# Joystick-Minikarte.net
KiCad netlist of a schematic drawn in EAGLE
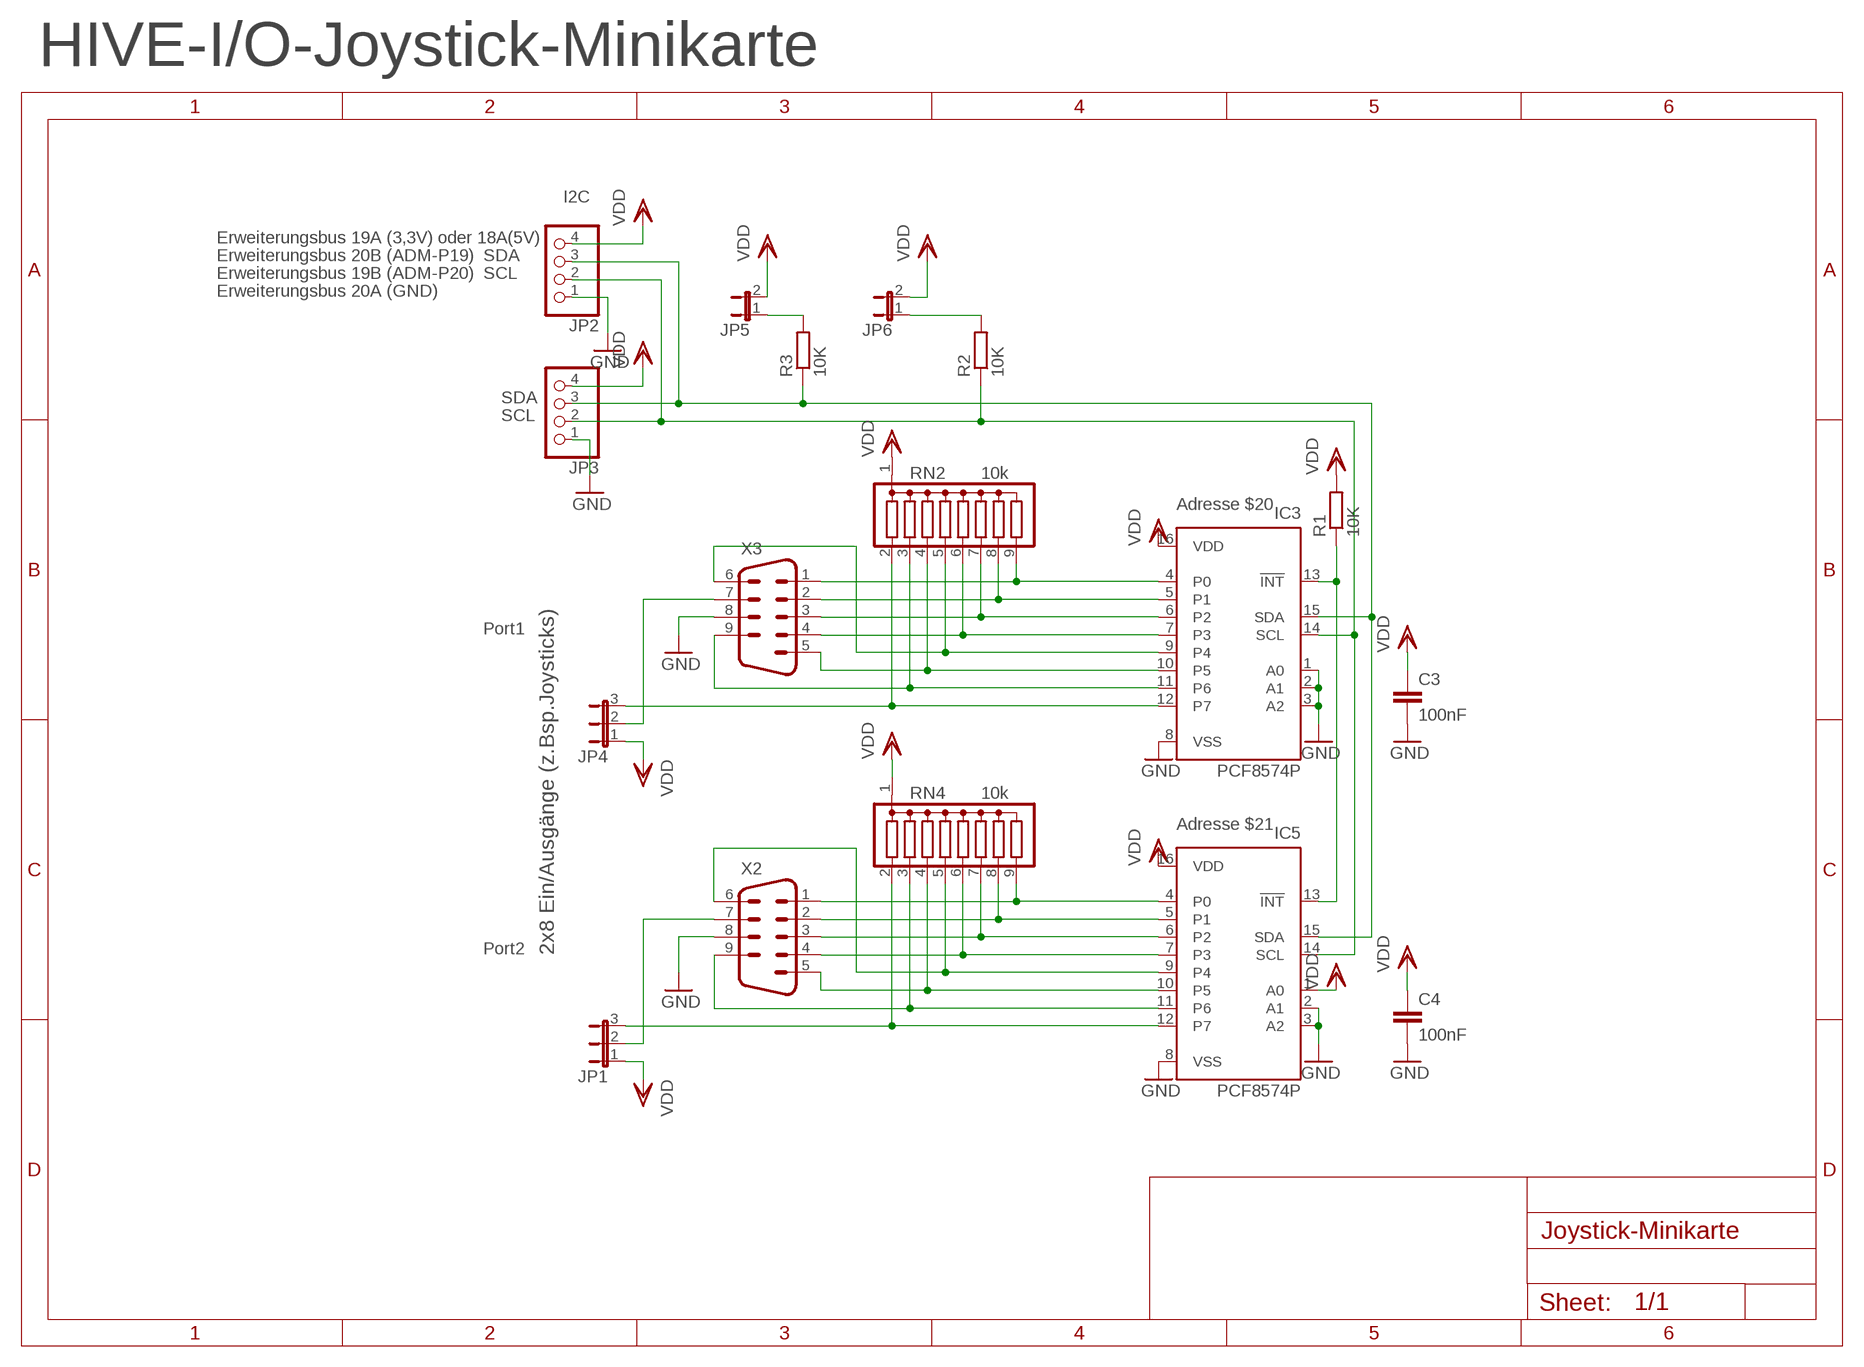
[diagram p0: schematic, sheet 1]

(export (version "E")
  (design (tool "Eeschema 10.0.6"))
  (components
    (comp (ref "C3")
      (value "100nF")
      (footprint "eagle-import:C025-024X044")
      (libsource (lib "eagle-import") (part "C-EU025-024X044"))
    )
    (comp (ref "C4")
      (value "100nF")
      (footprint "eagle-import:C025-024X044")
      (libsource (lib "eagle-import") (part "C-EU025-024X044"))
    )
    (comp (ref "IC3")
      (value "PCF8574P")
      (footprint "eagle-import:DIL16")
      (fields (field (name "MPN") "PCF8574PN"))
      (libsource (lib "eagle-import") (part "PCF8574P"))
    )
    (comp (ref "IC5")
      (value "PCF8574P")
      (footprint "eagle-import:DIL16")
      (fields
        (field (name "MPN") "PCF8574PN")
        (field (name "MPN_1") "PCF8574PN")
        (field (name "OC_FARNELL") "204020")
        (field (name "OC_NEWARK") "11N8515")
      )
      (libsource (lib "eagle-import") (part "PCF8574P"))
    )
    (comp (ref "JP1")
      (value "JP2E")
      (footprint "eagle-import:JP2")
      (libsource (lib "eagle-import") (part "JP2E"))
    )
    (comp (ref "JP2")
      (value "PINHD-1X4")
      (footprint "eagle-import:1X04")
      (libsource (lib "eagle-import") (part "PINHD-1X4"))
    )
    (comp (ref "JP3")
      (value "PINHD-1X4")
      (footprint "eagle-import:1X04")
      (libsource (lib "eagle-import") (part "PINHD-1X4"))
    )
    (comp (ref "JP4")
      (value "JP2E")
      (footprint "eagle-import:JP2")
      (libsource (lib "eagle-import") (part "JP2E"))
    )
    (comp (ref "JP5")
      (value "JP1E")
      (footprint "eagle-import:JP1")
      (libsource (lib "eagle-import") (part "JP1E"))
    )
    (comp (ref "JP6")
      (value "JP1E")
      (footprint "eagle-import:JP1")
      (libsource (lib "eagle-import") (part "JP1E"))
    )
    (comp (ref "R1")
      (value "10K")
      (footprint "eagle-import:0204_7")
      (libsource (lib "eagle-import") (part "R-EU_0204/7"))
    )
    (comp (ref "R2")
      (value "10K")
      (footprint "eagle-import:0204_7")
      (libsource (lib "eagle-import") (part "R-EU_0204/7"))
    )
    (comp (ref "R3")
      (value "10K")
      (footprint "eagle-import:0204_7")
      (libsource (lib "eagle-import") (part "R-EU_0204/7"))
    )
    (comp (ref "RN2")
      (value "10k")
      (footprint "eagle-import:SIL9")
      (libsource (lib "eagle-import") (part "G08R"))
    )
    (comp (ref "RN4")
      (value "10k")
      (footprint "eagle-import:SIL9")
      (libsource (lib "eagle-import") (part "G08R"))
    )
    (comp (ref "X2")
      (value "M09HP")
      (footprint "eagle-import:M09HP")
      (libsource (lib "eagle-import") (part "M09HP"))
    )
    (comp (ref "X3")
      (value "M09HP")
      (footprint "eagle-import:M09HP")
      (fields (field (name "OC_FARNELL") "unknown") (field (name "OC_NEWARK") "unknown"))
      (libsource (lib "eagle-import") (part "M09HP"))
    )
  )
  (nets
    (net (code "1") (name "GND") (class "Default")
      (node (ref "C3") (pin "2") (pinfunction "2_2") (pintype "passive"))
      (node (ref "C4") (pin "2") (pinfunction "2_2") (pintype "passive"))
      (node (ref "IC3") (pin "1") (pinfunction "A0_1") (pintype "input"))
      (node (ref "IC3") (pin "2") (pinfunction "A1_2") (pintype "input"))
      (node (ref "IC3") (pin "3") (pinfunction "A2_3") (pintype "input"))
      (node (ref "IC3") (pin "8") (pinfunction "VSS_8") (pintype "power_in"))
      (node (ref "IC5") (pin "2") (pinfunction "A1_2") (pintype "input"))
      (node (ref "IC5") (pin "3") (pinfunction "A2_3") (pintype "input"))
      (node (ref "IC5") (pin "8") (pinfunction "VSS_8") (pintype "power_in"))
      (node (ref "JP2") (pin "1") (pinfunction "1_1") (pintype "passive"))
      (node (ref "JP3") (pin "1") (pinfunction "1_1") (pintype "passive"))
      (node (ref "X2") (pin "8") (pinfunction "8_8") (pintype "passive"))
      (node (ref "X3") (pin "8") (pinfunction "8_8") (pintype "passive"))
    )
    (net (code "2") (name "Net-(IC3-P0)") (class "Default")
      (node (ref "IC3") (pin "4") (pinfunction "P0_4") (pintype "bidirectional"))
      (node (ref "RN2") (pin "9") (pinfunction "9_9") (pintype "passive"))
      (node (ref "X3") (pin "1") (pinfunction "1_1") (pintype "passive"))
    )
    (net (code "3") (name "Net-(IC3-P1)") (class "Default")
      (node (ref "IC3") (pin "5") (pinfunction "P1_5") (pintype "bidirectional"))
      (node (ref "RN2") (pin "8") (pinfunction "8_8") (pintype "passive"))
      (node (ref "X3") (pin "2") (pinfunction "2_2") (pintype "passive"))
    )
    (net (code "4") (name "Net-(IC3-P2)") (class "Default")
      (node (ref "IC3") (pin "6") (pinfunction "P2_6") (pintype "bidirectional"))
      (node (ref "RN2") (pin "7") (pinfunction "7_7") (pintype "passive"))
      (node (ref "X3") (pin "3") (pinfunction "3_3") (pintype "passive"))
    )
    (net (code "5") (name "Net-(IC3-P3)") (class "Default")
      (node (ref "IC3") (pin "7") (pinfunction "P3_7") (pintype "bidirectional"))
      (node (ref "RN2") (pin "6") (pinfunction "6_6") (pintype "passive"))
      (node (ref "X3") (pin "4") (pinfunction "4_4") (pintype "passive"))
    )
    (net (code "6") (name "Net-(IC3-P4)") (class "Default")
      (node (ref "IC3") (pin "9") (pinfunction "P4_9") (pintype "bidirectional"))
      (node (ref "RN2") (pin "5") (pinfunction "5_5") (pintype "passive"))
      (node (ref "X3") (pin "6") (pinfunction "6_6") (pintype "passive"))
    )
    (net (code "7") (name "Net-(IC3-P5)") (class "Default")
      (node (ref "IC3") (pin "10") (pinfunction "P5_10") (pintype "bidirectional"))
      (node (ref "RN2") (pin "4") (pinfunction "4_4") (pintype "passive"))
      (node (ref "X3") (pin "5") (pinfunction "5_5") (pintype "passive"))
    )
    (net (code "8") (name "Net-(IC3-P6)") (class "Default")
      (node (ref "IC3") (pin "11") (pinfunction "P6_11") (pintype "bidirectional"))
      (node (ref "RN2") (pin "3") (pinfunction "3_3") (pintype "passive"))
      (node (ref "X3") (pin "9") (pinfunction "9_9") (pintype "passive"))
    )
    (net (code "9") (name "Net-(IC3-P7)") (class "Default")
      (node (ref "IC3") (pin "12") (pinfunction "P7_12") (pintype "bidirectional"))
      (node (ref "JP4") (pin "3") (pinfunction "3_3") (pintype "passive"))
      (node (ref "RN2") (pin "2") (pinfunction "2_2") (pintype "passive"))
    )
    (net (code "10") (name "Net-(IC3-SCL)") (class "Default")
      (node (ref "IC3") (pin "14") (pinfunction "SCL_14") (pintype "input"))
      (node (ref "IC5") (pin "14") (pinfunction "SCL_14") (pintype "input"))
      (node (ref "JP2") (pin "2") (pinfunction "2_2") (pintype "passive"))
      (node (ref "JP3") (pin "2") (pinfunction "2_2") (pintype "passive"))
      (node (ref "R2") (pin "1") (pinfunction "1_1") (pintype "passive"))
    )
    (net (code "11") (name "Net-(IC3-SDA)") (class "Default")
      (node (ref "IC3") (pin "15") (pinfunction "SDA_15") (pintype "bidirectional"))
      (node (ref "IC5") (pin "15") (pinfunction "SDA_15") (pintype "bidirectional"))
      (node (ref "JP2") (pin "3") (pinfunction "3_3") (pintype "passive"))
      (node (ref "JP3") (pin "3") (pinfunction "3_3") (pintype "passive"))
      (node (ref "R3") (pin "1") (pinfunction "1_1") (pintype "passive"))
    )
    (net (code "12") (name "Net-(IC3-~{INT})") (class "Default")
      (node (ref "IC3") (pin "13") (pinfunction "~{INT}_13") (pintype "output"))
      (node (ref "IC5") (pin "13") (pinfunction "~{INT}_13") (pintype "output"))
      (node (ref "R1") (pin "1") (pinfunction "1_1") (pintype "passive"))
    )
    (net (code "13") (name "Net-(IC5-P0)") (class "Default")
      (node (ref "IC5") (pin "4") (pinfunction "P0_4") (pintype "bidirectional"))
      (node (ref "RN4") (pin "9") (pinfunction "9_9") (pintype "passive"))
      (node (ref "X2") (pin "1") (pinfunction "1_1") (pintype "passive"))
    )
    (net (code "14") (name "Net-(IC5-P1)") (class "Default")
      (node (ref "IC5") (pin "5") (pinfunction "P1_5") (pintype "bidirectional"))
      (node (ref "RN4") (pin "8") (pinfunction "8_8") (pintype "passive"))
      (node (ref "X2") (pin "2") (pinfunction "2_2") (pintype "passive"))
    )
    (net (code "15") (name "Net-(IC5-P2)") (class "Default")
      (node (ref "IC5") (pin "6") (pinfunction "P2_6") (pintype "bidirectional"))
      (node (ref "RN4") (pin "7") (pinfunction "7_7") (pintype "passive"))
      (node (ref "X2") (pin "3") (pinfunction "3_3") (pintype "passive"))
    )
    (net (code "16") (name "Net-(IC5-P3)") (class "Default")
      (node (ref "IC5") (pin "7") (pinfunction "P3_7") (pintype "bidirectional"))
      (node (ref "RN4") (pin "6") (pinfunction "6_6") (pintype "passive"))
      (node (ref "X2") (pin "4") (pinfunction "4_4") (pintype "passive"))
    )
    (net (code "17") (name "Net-(IC5-P4)") (class "Default")
      (node (ref "IC5") (pin "9") (pinfunction "P4_9") (pintype "bidirectional"))
      (node (ref "RN4") (pin "5") (pinfunction "5_5") (pintype "passive"))
      (node (ref "X2") (pin "6") (pinfunction "6_6") (pintype "passive"))
    )
    (net (code "18") (name "Net-(IC5-P5)") (class "Default")
      (node (ref "IC5") (pin "10") (pinfunction "P5_10") (pintype "bidirectional"))
      (node (ref "RN4") (pin "4") (pinfunction "4_4") (pintype "passive"))
      (node (ref "X2") (pin "5") (pinfunction "5_5") (pintype "passive"))
    )
    (net (code "19") (name "Net-(IC5-P6)") (class "Default")
      (node (ref "IC5") (pin "11") (pinfunction "P6_11") (pintype "bidirectional"))
      (node (ref "RN4") (pin "3") (pinfunction "3_3") (pintype "passive"))
      (node (ref "X2") (pin "9") (pinfunction "9_9") (pintype "passive"))
    )
    (net (code "20") (name "Net-(IC5-P7)") (class "Default")
      (node (ref "IC5") (pin "12") (pinfunction "P7_12") (pintype "bidirectional"))
      (node (ref "JP1") (pin "3") (pinfunction "3_3") (pintype "passive"))
      (node (ref "RN4") (pin "2") (pinfunction "2_2") (pintype "passive"))
    )
    (net (code "21") (name "Net-(JP1-Pad2)") (class "Default")
      (node (ref "JP1") (pin "2") (pinfunction "2_2") (pintype "passive"))
      (node (ref "X2") (pin "7") (pinfunction "7_7") (pintype "passive"))
    )
    (net (code "22") (name "Net-(JP4-Pad2)") (class "Default")
      (node (ref "JP4") (pin "2") (pinfunction "2_2") (pintype "passive"))
      (node (ref "X3") (pin "7") (pinfunction "7_7") (pintype "passive"))
    )
    (net (code "23") (name "Net-(JP5-Pad1)") (class "Default")
      (node (ref "JP5") (pin "1") (pinfunction "1_1") (pintype "passive"))
      (node (ref "R3") (pin "2") (pinfunction "2_2") (pintype "passive"))
    )
    (net (code "24") (name "Net-(JP6-Pad1)") (class "Default")
      (node (ref "JP6") (pin "1") (pinfunction "1_1") (pintype "passive"))
      (node (ref "R2") (pin "2") (pinfunction "2_2") (pintype "passive"))
    )
    (net (code "25") (name "VDD") (class "Default")
      (node (ref "C3") (pin "1") (pinfunction "1_1") (pintype "passive"))
      (node (ref "C4") (pin "1") (pinfunction "1_1") (pintype "passive"))
      (node (ref "IC3") (pin "16") (pinfunction "VDD_16") (pintype "power_in"))
      (node (ref "IC5") (pin "1") (pinfunction "A0_1") (pintype "input"))
      (node (ref "IC5") (pin "16") (pinfunction "VDD_16") (pintype "power_in"))
      (node (ref "JP1") (pin "1") (pinfunction "1_1") (pintype "passive"))
      (node (ref "JP2") (pin "4") (pinfunction "4_4") (pintype "passive"))
      (node (ref "JP3") (pin "4") (pinfunction "4_4") (pintype "passive"))
      (node (ref "JP4") (pin "1") (pinfunction "1_1") (pintype "passive"))
      (node (ref "JP5") (pin "2") (pinfunction "2_2") (pintype "passive"))
      (node (ref "JP6") (pin "2") (pinfunction "2_2") (pintype "passive"))
      (node (ref "R1") (pin "2") (pinfunction "2_2") (pintype "passive"))
      (node (ref "RN2") (pin "1") (pinfunction "1_1") (pintype "passive"))
      (node (ref "RN4") (pin "1") (pinfunction "1_1") (pintype "passive"))
    )
  )
)
